# 3_-_display.net
KiCad netlist of a schematic drawn in Altium Designer
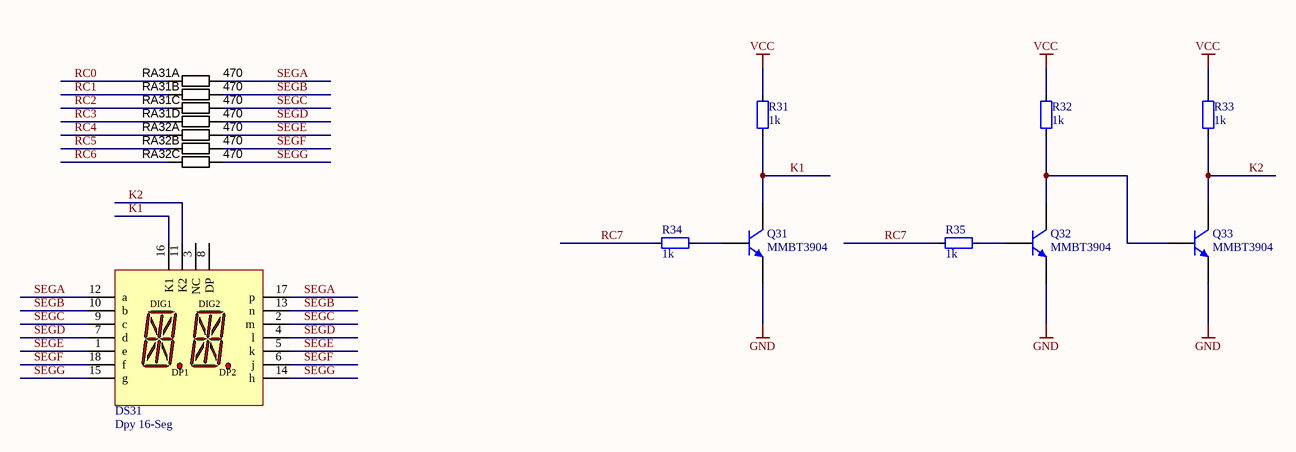
[diagram p0: 3 - display.SchDoc]

(export (version "E")
  (design (tool "Eeschema 10.0.6"))
  (components
    (comp (ref "DS31")
      (value "Dpy 16-Seg")
      (footprint "HDSP-A2")
      (description "13.7 mm Gray Surface As AlInGaP Red Alphanumeric Display: 2-Character, CC")
      (fields (field (name "PUBLISHER") "Altium Limited"))
      (libsource (lib "Miscellaneous Devices") (part "Dpy 16-Seg"))
    )
    (comp (ref "Q31")
      (value "MMBT3904")
      (footprint "SOT23_N")
      (description "NPN Switching Transistor")
      (fields (field (name "PUBLISHER") "Altium Limited"))
      (libsource (lib "Philips Discrete BJT - Low Power") (part "MMBT3904"))
    )
    (comp (ref "Q32")
      (value "MMBT3904")
      (footprint "SOT23_N")
      (description "NPN Switching Transistor")
      (fields (field (name "PUBLISHER") "Altium Limited"))
      (libsource (lib "Philips Discrete BJT - Low Power") (part "MMBT3904"))
    )
    (comp (ref "Q33")
      (value "MMBT3904")
      (footprint "SOT23_N")
      (description "NPN Switching Transistor")
      (fields (field (name "PUBLISHER") "Altium Limited"))
      (libsource (lib "Philips Discrete BJT - Low Power") (part "MMBT3904"))
    )
    (comp (ref "R31")
      (value "1k")
      (footprint "PCB_PassiveRes:RES_0603")
      (description "Resistor")
      (fields (field (name "Comment") "Res_0603"))
      (libsource (lib "") (part "Res_0603_1"))
    )
    (comp (ref "R32")
      (value "1k")
      (footprint "PCB_PassiveRes:RES_0603")
      (description "Resistor")
      (fields (field (name "Comment") "Res_0603"))
      (libsource (lib "") (part "Res_0603_1"))
    )
    (comp (ref "R33")
      (value "1k")
      (footprint "PCB_PassiveRes:RES_0603")
      (description "Resistor")
      (fields (field (name "Comment") "Res_0603"))
      (libsource (lib "") (part "Res_0603_1"))
    )
    (comp (ref "R34")
      (value "1k")
      (footprint "PCB_PassiveRes:RES_0603")
      (description "Resistor")
      (fields (field (name "Comment") "Res_0603"))
      (libsource (lib "SCH_Passive") (part "Res_0603"))
    )
    (comp (ref "R35")
      (value "1k")
      (footprint "PCB_PassiveRes:RES_0603")
      (description "Resistor")
      (fields (field (name "Comment") "Res_0603"))
      (libsource (lib "SCH_Passive") (part "Res_0603"))
    )
    (comp (ref "RA31")
      (value "470")
      (footprint "RESCAXS50P160X320X70-8N")
      (description "Resistor array 1K Ohm 4-pack 62.5mW 5% 4x1608 SMD")
      (fields (field (name "TOLERANCE") "±5%") (field (name "Comment") "Film Res Pack"))
      (libsource (lib "PBL - Resistors") (part "RESPACK_1K_5%_4X"))
    )
    (comp (ref "RA32")
      (value "470")
      (footprint "RESCAXS50P160X320X70-8N")
      (description "Resistor array 1K Ohm 4-pack 62.5mW 5% 4x1608 SMD")
      (fields (field (name "TOLERANCE") "±5%") (field (name "Comment") "Film Res Pack"))
      (libsource (lib "PBL - Resistors") (part "RESPACK_1K_5%_4X"))
    )
  )
  (nets
    (net (code "1") (name "/K1") (class "Default")
      (node (ref "DS31") (pin "16") (pinfunction "K1_16") (pintype "passive"))
      (node (ref "Q31") (pin "3") (pinfunction "C_3") (pintype "passive"))
      (node (ref "R31") (pin "1") (pinfunction "1_1") (pintype "passive"))
    )
    (net (code "2") (name "/K2") (class "Default")
      (node (ref "DS31") (pin "11") (pinfunction "K2_11") (pintype "passive"))
      (node (ref "Q33") (pin "3") (pinfunction "C_3") (pintype "passive"))
      (node (ref "R33") (pin "1") (pinfunction "1_1") (pintype "passive"))
    )
    (net (code "3") (name "/RC0") (class "Default")
      (node (ref "RA31") (pin "1") (pinfunction "1_1") (pintype "passive"))
    )
    (net (code "4") (name "/RC1") (class "Default")
      (node (ref "RA31") (pin "2") (pinfunction "2_2") (pintype "passive"))
    )
    (net (code "5") (name "/RC2") (class "Default")
      (node (ref "RA31") (pin "3") (pinfunction "3_3") (pintype "passive"))
    )
    (net (code "6") (name "/RC3") (class "Default")
      (node (ref "RA31") (pin "4") (pinfunction "4_4") (pintype "passive"))
    )
    (net (code "7") (name "/RC4") (class "Default")
      (node (ref "RA32") (pin "1") (pinfunction "1_1") (pintype "passive"))
    )
    (net (code "8") (name "/RC5") (class "Default")
      (node (ref "RA32") (pin "2") (pinfunction "2_2") (pintype "passive"))
    )
    (net (code "9") (name "/RC6") (class "Default")
      (node (ref "RA32") (pin "3") (pinfunction "3_3") (pintype "passive"))
    )
    (net (code "10") (name "/RC7") (class "Default")
      (node (ref "R34") (pin "2") (pinfunction "2_2") (pintype "passive"))
      (node (ref "R35") (pin "2") (pinfunction "2_2") (pintype "passive"))
    )
    (net (code "11") (name "/SEGA") (class "Default")
      (node (ref "DS31") (pin "12") (pinfunction "a_12") (pintype "passive"))
      (node (ref "DS31") (pin "17") (pinfunction "p_17") (pintype "passive"))
      (node (ref "RA31") (pin "8") (pinfunction "8_8") (pintype "passive"))
    )
    (net (code "12") (name "/SEGB") (class "Default")
      (node (ref "DS31") (pin "10") (pinfunction "b_10") (pintype "passive"))
      (node (ref "DS31") (pin "13") (pinfunction "n_13") (pintype "passive"))
      (node (ref "RA31") (pin "7") (pinfunction "7_7") (pintype "passive"))
    )
    (net (code "13") (name "/SEGC") (class "Default")
      (node (ref "DS31") (pin "2") (pinfunction "m_2") (pintype "passive"))
      (node (ref "DS31") (pin "9") (pinfunction "c_9") (pintype "passive"))
      (node (ref "RA31") (pin "6") (pinfunction "6_6") (pintype "passive"))
    )
    (net (code "14") (name "/SEGD") (class "Default")
      (node (ref "DS31") (pin "4") (pinfunction "l_4") (pintype "passive"))
      (node (ref "DS31") (pin "7") (pinfunction "d_7") (pintype "passive"))
      (node (ref "RA31") (pin "5") (pinfunction "5_5") (pintype "passive"))
    )
    (net (code "15") (name "/SEGE") (class "Default")
      (node (ref "DS31") (pin "1") (pinfunction "e_1") (pintype "passive"))
      (node (ref "DS31") (pin "5") (pinfunction "k_5") (pintype "passive"))
      (node (ref "RA32") (pin "8") (pinfunction "8_8") (pintype "passive"))
    )
    (net (code "16") (name "/SEGF") (class "Default")
      (node (ref "DS31") (pin "18") (pinfunction "f_18") (pintype "passive"))
      (node (ref "DS31") (pin "6") (pinfunction "j_6") (pintype "passive"))
      (node (ref "RA32") (pin "7") (pinfunction "7_7") (pintype "passive"))
    )
    (net (code "17") (name "/SEGG") (class "Default")
      (node (ref "DS31") (pin "14") (pinfunction "h_14") (pintype "passive"))
      (node (ref "DS31") (pin "15") (pinfunction "g_15") (pintype "passive"))
      (node (ref "RA32") (pin "6") (pinfunction "6_6") (pintype "passive"))
    )
    (net (code "18") (name "GND") (class "Default")
      (node (ref "Q31") (pin "2") (pinfunction "E_2") (pintype "passive"))
      (node (ref "Q32") (pin "2") (pinfunction "E_2") (pintype "passive"))
      (node (ref "Q33") (pin "2") (pinfunction "E_2") (pintype "passive"))
    )
    (net (code "19") (name "Net-(Q31-B)") (class "Default")
      (node (ref "Q31") (pin "1") (pinfunction "B_1") (pintype "passive"))
      (node (ref "R34") (pin "1") (pinfunction "1_1") (pintype "passive"))
    )
    (net (code "20") (name "Net-(Q32-B)") (class "Default")
      (node (ref "Q32") (pin "1") (pinfunction "B_1") (pintype "passive"))
      (node (ref "R35") (pin "1") (pinfunction "1_1") (pintype "passive"))
    )
    (net (code "21") (name "Net-(Q32-C)") (class "Default")
      (node (ref "Q32") (pin "3") (pinfunction "C_3") (pintype "passive"))
      (node (ref "Q33") (pin "1") (pinfunction "B_1") (pintype "passive"))
      (node (ref "R32") (pin "1") (pinfunction "1_1") (pintype "passive"))
    )
    (net (code "22") (name "VCC") (class "Default")
      (node (ref "R31") (pin "2") (pinfunction "2_2") (pintype "passive"))
      (node (ref "R32") (pin "2") (pinfunction "2_2") (pintype "passive"))
      (node (ref "R33") (pin "2") (pinfunction "2_2") (pintype "passive"))
    )
    (net (code "23") (name "unconnected-(DS31-DP-Pad8)") (class "Default")
      (node (ref "DS31") (pin "8") (pinfunction "DP_8") (pintype "passive"))
    )
    (net (code "24") (name "unconnected-(DS31-NC-Pad3)") (class "Default")
      (node (ref "DS31") (pin "3") (pinfunction "NC_3") (pintype "passive"))
    )
  )
)
